# statuspanel.net
KiCad netlist of a schematic drawn in EAGLE
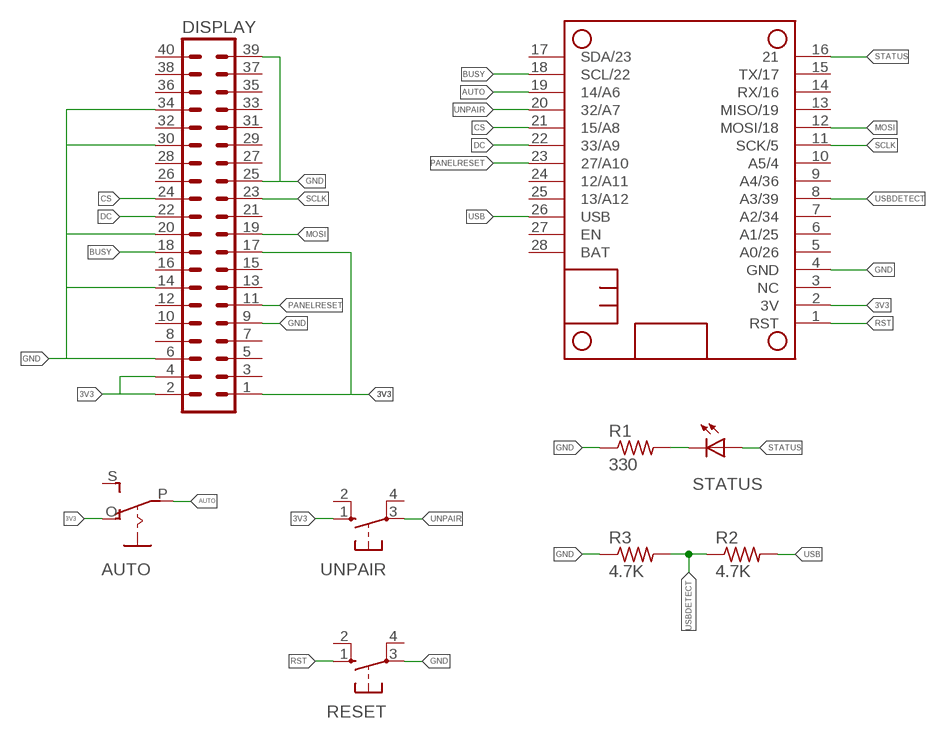
[diagram p0: schematic, sheet 1]

(export (version "E")
  (design (tool "Eeschema 10.0.6"))
  (components
    (comp (ref "AUTO")
      (value "EG1218S")
      (footprint "eagle-import:EG1218")
      (libsource (lib "eagle-import") (part "EG1218S"))
    )
    (comp (ref "DISPLAY")
      (value "MA20-2")
      (footprint "eagle-import:MA20-2")
      (libsource (lib "eagle-import") (part "MA20-2"))
    )
    (comp (ref "HUZZAH32")
      (value "HUZZAH32_NODIM")
      (footprint "eagle-import:FEATHERWING_DIM")
      (libsource (lib "eagle-import") (part "HUZZAH32_NODIM"))
    )
    (comp (ref "R1")
      (value "330")
      (footprint "eagle-import:R0805")
      (libsource (lib "eagle-import") (part "R-US_R0805"))
    )
    (comp (ref "R2")
      (value "4.7K")
      (footprint "eagle-import:R0805")
      (libsource (lib "eagle-import") (part "R-US_R0805"))
    )
    (comp (ref "R3")
      (value "4.7K")
      (footprint "eagle-import:R0805")
      (libsource (lib "eagle-import") (part "R-US_R0805"))
    )
    (comp (ref "RESET")
      (value "10-XX")
      (footprint "eagle-import:B3F-10XX")
      (fields (field (name "MPN") "B3F-1000"))
      (libsource (lib "eagle-import") (part "10-XX"))
    )
    (comp (ref "STATUS")
      (value "LED3MM")
      (footprint "eagle-import:LED3MM")
      (libsource (lib "eagle-import") (part "LED3MM"))
    )
    (comp (ref "UNPAIR")
      (value "10-XX")
      (footprint "eagle-import:B3F-10XX")
      (fields (field (name "MPN") "B3F-1000"))
      (libsource (lib "eagle-import") (part "10-XX"))
    )
  )
  (nets
    (net (code "1") (name "/BAT") (class "Default")
      (node (ref "HUZZAH32") (pin "28") (pinfunction "BAT_28") (pintype "power_in"))
    )
    (net (code "2") (name "3V3") (class "Default")
      (node (ref "AUTO") (pin "O") (pinfunction "O_O") (pintype "passive"))
      (node (ref "DISPLAY") (pin "1") (pinfunction "1_1") (pintype "passive"))
      (node (ref "DISPLAY") (pin "17") (pinfunction "17_17") (pintype "passive"))
      (node (ref "DISPLAY") (pin "2") (pinfunction "2_2") (pintype "passive"))
      (node (ref "DISPLAY") (pin "4") (pinfunction "4_4") (pintype "passive"))
      (node (ref "HUZZAH32") (pin "2") (pinfunction "3V_2") (pintype "power_in"))
      (node (ref "UNPAIR") (pin "1") (pinfunction "S_1") (pintype "passive"))
    )
    (net (code "3") (name "AUTO") (class "Default")
      (node (ref "AUTO") (pin "P") (pinfunction "P_P") (pintype "passive"))
      (node (ref "HUZZAH32") (pin "19") (pinfunction "14/A6_19") (pintype "bidirectional"))
    )
    (net (code "4") (name "BUSY") (class "Default")
      (node (ref "DISPLAY") (pin "18") (pinfunction "18_18") (pintype "passive"))
      (node (ref "HUZZAH32") (pin "18") (pinfunction "SCL/22_18") (pintype "bidirectional"))
    )
    (net (code "5") (name "CS") (class "Default")
      (node (ref "DISPLAY") (pin "24") (pinfunction "24_24") (pintype "passive"))
      (node (ref "HUZZAH32") (pin "21") (pinfunction "15/A8_21") (pintype "bidirectional"))
    )
    (net (code "6") (name "DC") (class "Default")
      (node (ref "DISPLAY") (pin "22") (pinfunction "22_22") (pintype "passive"))
      (node (ref "HUZZAH32") (pin "22") (pinfunction "33/A9_22") (pintype "bidirectional"))
    )
    (net (code "7") (name "GND") (class "Default")
      (node (ref "DISPLAY") (pin "14") (pinfunction "14_14") (pintype "passive"))
      (node (ref "DISPLAY") (pin "20") (pinfunction "20_20") (pintype "passive"))
      (node (ref "DISPLAY") (pin "25") (pinfunction "25_25") (pintype "passive"))
      (node (ref "DISPLAY") (pin "30") (pinfunction "30_30") (pintype "passive"))
      (node (ref "DISPLAY") (pin "34") (pinfunction "34_34") (pintype "passive"))
      (node (ref "DISPLAY") (pin "39") (pinfunction "39_39") (pintype "passive"))
      (node (ref "DISPLAY") (pin "6") (pinfunction "6_6") (pintype "passive"))
      (node (ref "DISPLAY") (pin "9") (pinfunction "9_9") (pintype "passive"))
      (node (ref "HUZZAH32") (pin "4") (pinfunction "GND_4") (pintype "power_in"))
      (node (ref "R1") (pin "1") (pinfunction "1_1") (pintype "passive"))
      (node (ref "R3") (pin "1") (pinfunction "1_1") (pintype "passive"))
      (node (ref "RESET") (pin "3") (pinfunction "P_3") (pintype "passive"))
    )
    (net (code "8") (name "MOSI") (class "Default")
      (node (ref "DISPLAY") (pin "19") (pinfunction "19_19") (pintype "passive"))
      (node (ref "HUZZAH32") (pin "12") (pinfunction "MOSI/18_12") (pintype "bidirectional"))
    )
    (net (code "9") (name "Net-(STATUS-C)") (class "Default")
      (node (ref "R1") (pin "2") (pinfunction "2_2") (pintype "passive"))
      (node (ref "STATUS") (pin "K") (pinfunction "C_K") (pintype "passive"))
    )
    (net (code "10") (name "PANELRESET") (class "Default")
      (node (ref "DISPLAY") (pin "11") (pinfunction "11_11") (pintype "passive"))
      (node (ref "HUZZAH32") (pin "23") (pinfunction "27/A10_23") (pintype "bidirectional"))
    )
    (net (code "11") (name "RST") (class "Default")
      (node (ref "HUZZAH32") (pin "1") (pinfunction "RST_1") (pintype "input"))
      (node (ref "RESET") (pin "1") (pinfunction "S_1") (pintype "passive"))
    )
    (net (code "12") (name "SCLK") (class "Default")
      (node (ref "DISPLAY") (pin "23") (pinfunction "23_23") (pintype "passive"))
      (node (ref "HUZZAH32") (pin "11") (pinfunction "SCK/5_11") (pintype "bidirectional"))
    )
    (net (code "13") (name "STATUS") (class "Default")
      (node (ref "HUZZAH32") (pin "16") (pinfunction "21_16") (pintype "bidirectional"))
      (node (ref "STATUS") (pin "A") (pinfunction "A_A") (pintype "passive"))
    )
    (net (code "14") (name "UNPAIR") (class "Default")
      (node (ref "HUZZAH32") (pin "20") (pinfunction "32/A7_20") (pintype "bidirectional"))
      (node (ref "UNPAIR") (pin "3") (pinfunction "P_3") (pintype "passive"))
    )
    (net (code "15") (name "USB") (class "Default")
      (node (ref "HUZZAH32") (pin "26") (pinfunction "USB_26") (pintype "power_in"))
      (node (ref "R2") (pin "2") (pinfunction "2_2") (pintype "passive"))
    )
    (net (code "16") (name "USBDETECT") (class "Default")
      (node (ref "HUZZAH32") (pin "8") (pinfunction "A3/39_8") (pintype "bidirectional"))
      (node (ref "R2") (pin "1") (pinfunction "1_1") (pintype "passive"))
      (node (ref "R3") (pin "2") (pinfunction "2_2") (pintype "passive"))
    )
    (net (code "17") (name "unconnected-(AUTO-PadS)") (class "Default")
      (node (ref "AUTO") (pin "S") (pinfunction "S_S") (pintype "passive"))
    )
    (net (code "18") (name "unconnected-(DISPLAY-Pad3)") (class "Default")
      (node (ref "DISPLAY") (pin "3") (pinfunction "3_3") (pintype "passive"))
    )
    (net (code "19") (name "unconnected-(DISPLAY-Pad5)") (class "Default")
      (node (ref "DISPLAY") (pin "5") (pinfunction "5_5") (pintype "passive"))
    )
    (net (code "20") (name "unconnected-(DISPLAY-Pad7)") (class "Default")
      (node (ref "DISPLAY") (pin "7") (pinfunction "7_7") (pintype "passive"))
    )
    (net (code "21") (name "unconnected-(DISPLAY-Pad8)") (class "Default")
      (node (ref "DISPLAY") (pin "8") (pinfunction "8_8") (pintype "passive"))
    )
    (net (code "22") (name "unconnected-(DISPLAY-Pad10)") (class "Default")
      (node (ref "DISPLAY") (pin "10") (pinfunction "10_10") (pintype "passive"))
    )
    (net (code "23") (name "unconnected-(DISPLAY-Pad12)") (class "Default")
      (node (ref "DISPLAY") (pin "12") (pinfunction "12_12") (pintype "passive"))
    )
    (net (code "24") (name "unconnected-(DISPLAY-Pad13)") (class "Default")
      (node (ref "DISPLAY") (pin "13") (pinfunction "13_13") (pintype "passive"))
    )
    (net (code "25") (name "unconnected-(DISPLAY-Pad15)") (class "Default")
      (node (ref "DISPLAY") (pin "15") (pinfunction "15_15") (pintype "passive"))
    )
    (net (code "26") (name "unconnected-(DISPLAY-Pad16)") (class "Default")
      (node (ref "DISPLAY") (pin "16") (pinfunction "16_16") (pintype "passive"))
    )
    (net (code "27") (name "unconnected-(DISPLAY-Pad21)") (class "Default")
      (node (ref "DISPLAY") (pin "21") (pinfunction "21_21") (pintype "passive"))
    )
    (net (code "28") (name "unconnected-(DISPLAY-Pad26)") (class "Default")
      (node (ref "DISPLAY") (pin "26") (pinfunction "26_26") (pintype "passive"))
    )
    (net (code "29") (name "unconnected-(DISPLAY-Pad27)") (class "Default")
      (node (ref "DISPLAY") (pin "27") (pinfunction "27_27") (pintype "passive"))
    )
    (net (code "30") (name "unconnected-(DISPLAY-Pad28)") (class "Default")
      (node (ref "DISPLAY") (pin "28") (pinfunction "28_28") (pintype "passive"))
    )
    (net (code "31") (name "unconnected-(DISPLAY-Pad29)") (class "Default")
      (node (ref "DISPLAY") (pin "29") (pinfunction "29_29") (pintype "passive"))
    )
    (net (code "32") (name "unconnected-(DISPLAY-Pad31)") (class "Default")
      (node (ref "DISPLAY") (pin "31") (pinfunction "31_31") (pintype "passive"))
    )
    (net (code "33") (name "unconnected-(DISPLAY-Pad32)") (class "Default")
      (node (ref "DISPLAY") (pin "32") (pinfunction "32_32") (pintype "passive"))
    )
    (net (code "34") (name "unconnected-(DISPLAY-Pad33)") (class "Default")
      (node (ref "DISPLAY") (pin "33") (pinfunction "33_33") (pintype "passive"))
    )
    (net (code "35") (name "unconnected-(DISPLAY-Pad35)") (class "Default")
      (node (ref "DISPLAY") (pin "35") (pinfunction "35_35") (pintype "passive"))
    )
    (net (code "36") (name "unconnected-(DISPLAY-Pad36)") (class "Default")
      (node (ref "DISPLAY") (pin "36") (pinfunction "36_36") (pintype "passive"))
    )
    (net (code "37") (name "unconnected-(DISPLAY-Pad37)") (class "Default")
      (node (ref "DISPLAY") (pin "37") (pinfunction "37_37") (pintype "passive"))
    )
    (net (code "38") (name "unconnected-(DISPLAY-Pad38)") (class "Default")
      (node (ref "DISPLAY") (pin "38") (pinfunction "38_38") (pintype "passive"))
    )
    (net (code "39") (name "unconnected-(DISPLAY-Pad40)") (class "Default")
      (node (ref "DISPLAY") (pin "40") (pinfunction "40_40") (pintype "passive"))
    )
    (net (code "40") (name "unconnected-(HUZZAH32-12{slash}A11-Pad24)") (class "Default")
      (node (ref "HUZZAH32") (pin "24") (pinfunction "12/A11_24") (pintype "bidirectional"))
    )
    (net (code "41") (name "unconnected-(HUZZAH32-13{slash}A12-Pad25)") (class "Default")
      (node (ref "HUZZAH32") (pin "25") (pinfunction "13/A12_25") (pintype "bidirectional"))
    )
    (net (code "42") (name "unconnected-(HUZZAH32-A0{slash}26-Pad5)") (class "Default")
      (node (ref "HUZZAH32") (pin "5") (pinfunction "A0/26_5") (pintype "bidirectional"))
    )
    (net (code "43") (name "unconnected-(HUZZAH32-A1{slash}25-Pad6)") (class "Default")
      (node (ref "HUZZAH32") (pin "6") (pinfunction "A1/25_6") (pintype "bidirectional"))
    )
    (net (code "44") (name "unconnected-(HUZZAH32-A2{slash}34-Pad7)") (class "Default")
      (node (ref "HUZZAH32") (pin "7") (pinfunction "A2/34_7") (pintype "bidirectional"))
    )
    (net (code "45") (name "unconnected-(HUZZAH32-A4{slash}36-Pad9)") (class "Default")
      (node (ref "HUZZAH32") (pin "9") (pinfunction "A4/36_9") (pintype "bidirectional"))
    )
    (net (code "46") (name "unconnected-(HUZZAH32-A5{slash}4-Pad10)") (class "Default")
      (node (ref "HUZZAH32") (pin "10") (pinfunction "A5/4_10") (pintype "bidirectional"))
    )
    (net (code "47") (name "unconnected-(HUZZAH32-EN-Pad27)") (class "Default")
      (node (ref "HUZZAH32") (pin "27") (pinfunction "EN_27") (pintype "passive"))
    )
    (net (code "48") (name "unconnected-(HUZZAH32-MISO{slash}19-Pad13)") (class "Default")
      (node (ref "HUZZAH32") (pin "13") (pinfunction "MISO/19_13") (pintype "bidirectional"))
    )
    (net (code "49") (name "unconnected-(HUZZAH32-NC-Pad3)") (class "Default")
      (node (ref "HUZZAH32") (pin "3") (pinfunction "NC_3") (pintype "passive"))
    )
    (net (code "50") (name "unconnected-(HUZZAH32-RX{slash}16-Pad14)") (class "Default")
      (node (ref "HUZZAH32") (pin "14") (pinfunction "RX/16_14") (pintype "bidirectional"))
    )
    (net (code "51") (name "unconnected-(HUZZAH32-SDA{slash}23-Pad17)") (class "Default")
      (node (ref "HUZZAH32") (pin "17") (pinfunction "SDA/23_17") (pintype "bidirectional"))
    )
    (net (code "52") (name "unconnected-(HUZZAH32-TX{slash}17-Pad15)") (class "Default")
      (node (ref "HUZZAH32") (pin "15") (pinfunction "TX/17_15") (pintype "bidirectional"))
    )
    (net (code "53") (name "unconnected-(RESET-P1-Pad4)") (class "Default")
      (node (ref "RESET") (pin "4") (pinfunction "P1_4") (pintype "passive"))
    )
    (net (code "54") (name "unconnected-(RESET-S1-Pad2)") (class "Default")
      (node (ref "RESET") (pin "2") (pinfunction "S1_2") (pintype "passive"))
    )
    (net (code "55") (name "unconnected-(UNPAIR-P1-Pad4)") (class "Default")
      (node (ref "UNPAIR") (pin "4") (pinfunction "P1_4") (pintype "passive"))
    )
    (net (code "56") (name "unconnected-(UNPAIR-S1-Pad2)") (class "Default")
      (node (ref "UNPAIR") (pin "2") (pinfunction "S1_2") (pintype "passive"))
    )
  )
)
